# MAM_GND_V4.net
KiCad netlist of a schematic drawn in EAGLE
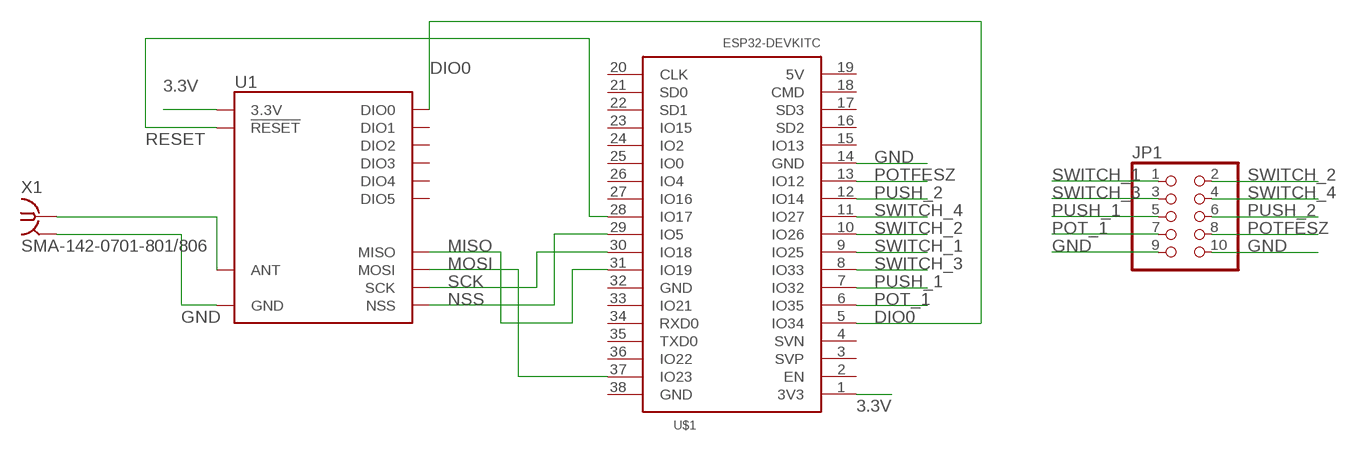
[diagram p0: schematic, sheet 1]

(export (version "E")
  (design (tool "Eeschema 10.0.6"))
  (components
    (comp (ref "JP1")
      (value "PINHD-2X5")
      (footprint "eagle-import:2X05")
      (libsource (lib "eagle-import") (part "PINHD-2X5"))
    )
    (comp (ref "U$1")
      (value "ESP32DEVKITC")
      (footprint "eagle-import:ESP32-DEVKITC")
      (libsource (lib "eagle-import") (part "ESP32DEVKITC"))
    )
    (comp (ref "U1")
      (value "RFM95W")
      (footprint "eagle-import:RFM95_96_97_98W")
      (libsource (lib "eagle-import") (part "RFM95W"))
    )
    (comp (ref "X1")
      (value "SMA-142-0701-801/806")
      (footprint "eagle-import:J502-ND-142-0701-801_806")
      (fields (field (name "MF") "JOHNSON COMPONENTS") (field (name "MPN") "142-0701-801"))
      (libsource (lib "eagle-import") (part "SMA-142-0701-801/806"))
    )
  )
  (nets
    (net (code "1") (name "/3.3V") (class "Default")
      (node (ref "U$1") (pin "1") (pinfunction "3V3_1") (pintype "bidirectional"))
      (node (ref "U1") (pin "3.3V") (pinfunction "3.3V_3.3V") (pintype "bidirectional"))
    )
    (net (code "2") (name "/DIO0") (class "Default")
      (node (ref "U$1") (pin "5") (pinfunction "IO34_5") (pintype "bidirectional"))
      (node (ref "U1") (pin "DIO0") (pinfunction "DIO0_DIO0") (pintype "bidirectional"))
    )
    (net (code "3") (name "/GND") (class "Default")
      (node (ref "JP1") (pin "10") (pinfunction "10_10") (pintype "passive"))
      (node (ref "JP1") (pin "9") (pinfunction "9_9") (pintype "passive"))
      (node (ref "U$1") (pin "14") (pinfunction "GND_14") (pintype "bidirectional"))
      (node (ref "U1") (pin "GND@1") (pinfunction "GND_GND@1") (pintype "bidirectional"))
      (node (ref "U1") (pin "GND@2") (pinfunction "GND_GND@2") (pintype "bidirectional"))
      (node (ref "U1") (pin "GND@3") (pinfunction "GND_GND@3") (pintype "bidirectional"))
      (node (ref "X1") (pin "G@1") (pinfunction "2_G@1") (pintype "passive"))
      (node (ref "X1") (pin "G@2") (pinfunction "2_G@2") (pintype "passive"))
      (node (ref "X1") (pin "G@3") (pinfunction "2_G@3") (pintype "passive"))
      (node (ref "X1") (pin "G@4") (pinfunction "2_G@4") (pintype "passive"))
    )
    (net (code "4") (name "/MISO") (class "Default")
      (node (ref "U$1") (pin "31") (pinfunction "IO19_31") (pintype "bidirectional"))
      (node (ref "U1") (pin "MISO") (pinfunction "MISO_MISO") (pintype "bidirectional"))
    )
    (net (code "5") (name "/MOSI") (class "Default")
      (node (ref "U$1") (pin "37") (pinfunction "IO23_37") (pintype "bidirectional"))
      (node (ref "U1") (pin "MOSI") (pinfunction "MOSI_MOSI") (pintype "bidirectional"))
    )
    (net (code "6") (name "/NSS") (class "Default")
      (node (ref "U$1") (pin "29") (pinfunction "IO5_29") (pintype "bidirectional"))
      (node (ref "U1") (pin "NSS") (pinfunction "NSS_NSS") (pintype "bidirectional"))
    )
    (net (code "7") (name "/POTFESZ") (class "Default")
      (node (ref "JP1") (pin "8") (pinfunction "8_8") (pintype "passive"))
      (node (ref "U$1") (pin "13") (pinfunction "IO12_13") (pintype "bidirectional"))
    )
    (net (code "8") (name "/POT_1") (class "Default")
      (node (ref "JP1") (pin "7") (pinfunction "7_7") (pintype "passive"))
      (node (ref "U$1") (pin "6") (pinfunction "IO35_6") (pintype "bidirectional"))
    )
    (net (code "9") (name "/PUSH_1") (class "Default")
      (node (ref "JP1") (pin "5") (pinfunction "5_5") (pintype "passive"))
      (node (ref "U$1") (pin "7") (pinfunction "IO32_7") (pintype "bidirectional"))
    )
    (net (code "10") (name "/PUSH_2") (class "Default")
      (node (ref "JP1") (pin "6") (pinfunction "6_6") (pintype "passive"))
      (node (ref "U$1") (pin "12") (pinfunction "IO14_12") (pintype "bidirectional"))
    )
    (net (code "11") (name "/RESET") (class "Default")
      (node (ref "U$1") (pin "28") (pinfunction "IO17_28") (pintype "bidirectional"))
      (node (ref "U1") (pin "!RESET") (pinfunction "~{RESET}_!RESET") (pintype "bidirectional"))
    )
    (net (code "12") (name "/SCK") (class "Default")
      (node (ref "U$1") (pin "30") (pinfunction "IO18_30") (pintype "bidirectional"))
      (node (ref "U1") (pin "SCK") (pinfunction "SCK_SCK") (pintype "bidirectional"))
    )
    (net (code "13") (name "/SWITCH_1") (class "Default")
      (node (ref "JP1") (pin "1") (pinfunction "1_1") (pintype "passive"))
      (node (ref "U$1") (pin "9") (pinfunction "IO25_9") (pintype "bidirectional"))
    )
    (net (code "14") (name "/SWITCH_2") (class "Default")
      (node (ref "JP1") (pin "2") (pinfunction "2_2") (pintype "passive"))
      (node (ref "U$1") (pin "10") (pinfunction "IO26_10") (pintype "bidirectional"))
    )
    (net (code "15") (name "/SWITCH_3") (class "Default")
      (node (ref "JP1") (pin "3") (pinfunction "3_3") (pintype "passive"))
      (node (ref "U$1") (pin "8") (pinfunction "IO33_8") (pintype "bidirectional"))
    )
    (net (code "16") (name "/SWITCH_4") (class "Default")
      (node (ref "JP1") (pin "4") (pinfunction "4_4") (pintype "passive"))
      (node (ref "U$1") (pin "11") (pinfunction "IO27_11") (pintype "bidirectional"))
    )
    (net (code "17") (name "Net-(U1-PadANT)") (class "Default")
      (node (ref "U1") (pin "ANT") (pinfunction "ANT_ANT") (pintype "bidirectional"))
      (node (ref "X1") (pin "1") (pinfunction "1_1") (pintype "passive"))
    )
    (net (code "18") (name "unconnected-(U$1-5V-Pad19)") (class "Default")
      (node (ref "U$1") (pin "19") (pinfunction "5V_19") (pintype "bidirectional"))
    )
    (net (code "19") (name "unconnected-(U$1-CLK-Pad20)") (class "Default")
      (node (ref "U$1") (pin "20") (pinfunction "CLK_20") (pintype "bidirectional"))
    )
    (net (code "20") (name "unconnected-(U$1-CMD-Pad18)") (class "Default")
      (node (ref "U$1") (pin "18") (pinfunction "CMD_18") (pintype "bidirectional"))
    )
    (net (code "21") (name "unconnected-(U$1-EN-Pad2)") (class "Default")
      (node (ref "U$1") (pin "2") (pinfunction "EN_2") (pintype "bidirectional"))
    )
    (net (code "22") (name "unconnected-(U$1-GND-Pad32)") (class "Default")
      (node (ref "U$1") (pin "32") (pinfunction "GND_32") (pintype "bidirectional"))
    )
    (net (code "23") (name "unconnected-(U$1-GND-Pad38)") (class "Default")
      (node (ref "U$1") (pin "38") (pinfunction "GND_38") (pintype "bidirectional"))
    )
    (net (code "24") (name "unconnected-(U$1-IO0-Pad25)") (class "Default")
      (node (ref "U$1") (pin "25") (pinfunction "IO0_25") (pintype "bidirectional"))
    )
    (net (code "25") (name "unconnected-(U$1-IO2-Pad24)") (class "Default")
      (node (ref "U$1") (pin "24") (pinfunction "IO2_24") (pintype "bidirectional"))
    )
    (net (code "26") (name "unconnected-(U$1-IO4-Pad26)") (class "Default")
      (node (ref "U$1") (pin "26") (pinfunction "IO4_26") (pintype "bidirectional"))
    )
    (net (code "27") (name "unconnected-(U$1-IO13-Pad15)") (class "Default")
      (node (ref "U$1") (pin "15") (pinfunction "IO13_15") (pintype "bidirectional"))
    )
    (net (code "28") (name "unconnected-(U$1-IO15-Pad23)") (class "Default")
      (node (ref "U$1") (pin "23") (pinfunction "IO15_23") (pintype "bidirectional"))
    )
    (net (code "29") (name "unconnected-(U$1-IO16-Pad27)") (class "Default")
      (node (ref "U$1") (pin "27") (pinfunction "IO16_27") (pintype "bidirectional"))
    )
    (net (code "30") (name "unconnected-(U$1-IO21-Pad33)") (class "Default")
      (node (ref "U$1") (pin "33") (pinfunction "IO21_33") (pintype "bidirectional"))
    )
    (net (code "31") (name "unconnected-(U$1-IO22-Pad36)") (class "Default")
      (node (ref "U$1") (pin "36") (pinfunction "IO22_36") (pintype "bidirectional"))
    )
    (net (code "32") (name "unconnected-(U$1-RXD0-Pad34)") (class "Default")
      (node (ref "U$1") (pin "34") (pinfunction "RXD0_34") (pintype "bidirectional"))
    )
    (net (code "33") (name "unconnected-(U$1-SD0-Pad21)") (class "Default")
      (node (ref "U$1") (pin "21") (pinfunction "SD0_21") (pintype "bidirectional"))
    )
    (net (code "34") (name "unconnected-(U$1-SD1-Pad22)") (class "Default")
      (node (ref "U$1") (pin "22") (pinfunction "SD1_22") (pintype "bidirectional"))
    )
    (net (code "35") (name "unconnected-(U$1-SD2-Pad16)") (class "Default")
      (node (ref "U$1") (pin "16") (pinfunction "SD2_16") (pintype "bidirectional"))
    )
    (net (code "36") (name "unconnected-(U$1-SD3-Pad17)") (class "Default")
      (node (ref "U$1") (pin "17") (pinfunction "SD3_17") (pintype "bidirectional"))
    )
    (net (code "37") (name "unconnected-(U$1-SVN-Pad4)") (class "Default")
      (node (ref "U$1") (pin "4") (pinfunction "SVN_4") (pintype "bidirectional"))
    )
    (net (code "38") (name "unconnected-(U$1-SVP-Pad3)") (class "Default")
      (node (ref "U$1") (pin "3") (pinfunction "SVP_3") (pintype "bidirectional"))
    )
    (net (code "39") (name "unconnected-(U$1-TXD0-Pad35)") (class "Default")
      (node (ref "U$1") (pin "35") (pinfunction "TXD0_35") (pintype "bidirectional"))
    )
    (net (code "40") (name "unconnected-(U1-PadDIO1)") (class "Default")
      (node (ref "U1") (pin "DIO1") (pinfunction "DIO1_DIO1") (pintype "bidirectional"))
    )
    (net (code "41") (name "unconnected-(U1-PadDIO2)") (class "Default")
      (node (ref "U1") (pin "DIO2") (pinfunction "DIO2_DIO2") (pintype "bidirectional"))
    )
    (net (code "42") (name "unconnected-(U1-PadDIO3)") (class "Default")
      (node (ref "U1") (pin "DIO3") (pinfunction "DIO3_DIO3") (pintype "bidirectional"))
    )
    (net (code "43") (name "unconnected-(U1-PadDIO4)") (class "Default")
      (node (ref "U1") (pin "DIO4") (pinfunction "DIO4_DIO4") (pintype "bidirectional"))
    )
    (net (code "44") (name "unconnected-(U1-PadDIO5)") (class "Default")
      (node (ref "U1") (pin "DIO5") (pinfunction "DIO5_DIO5") (pintype "bidirectional"))
    )
  )
)
